# Remote.net
KiCad netlist of a schematic drawn in EAGLE
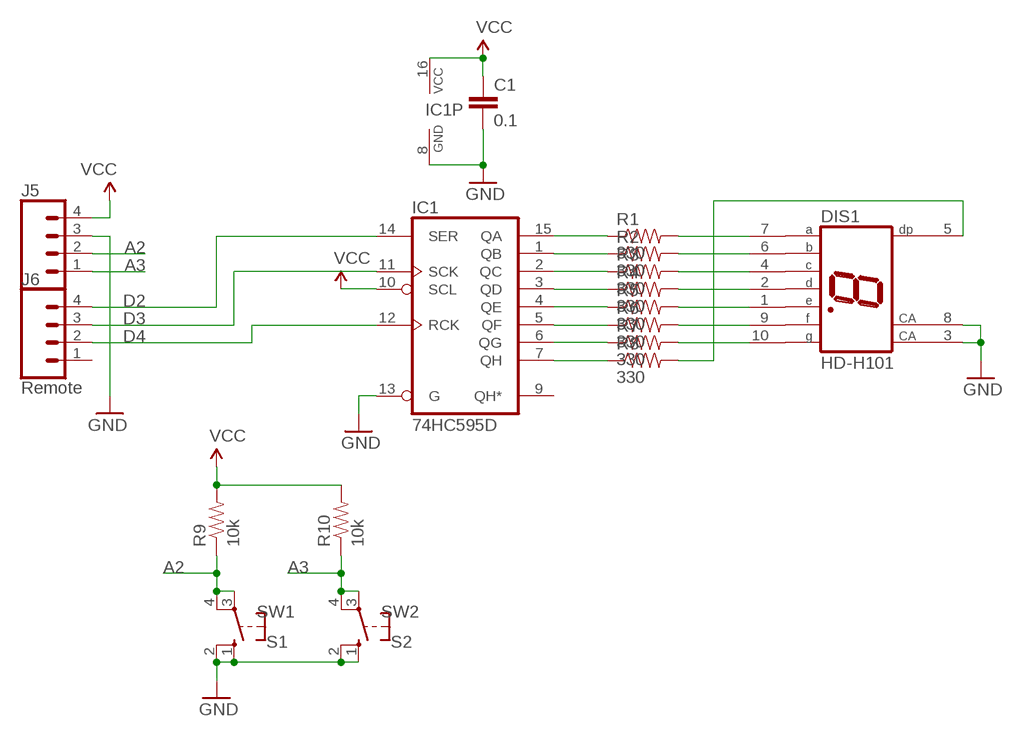
[diagram p0: schematic, sheet 1]

(export (version "E")
  (design (tool "Eeschema 10.0.6"))
  (components
    (comp (ref "C1")
      (value "0.1")
      (footprint "eagle-import:0805")
      (libsource (lib "eagle-import") (part "CAP0805"))
    )
    (comp (ref "DIS1")
      (value "HD-H101")
      (footprint "eagle-import:HDSP-M")
      (libsource (lib "eagle-import") (part "HD-H101"))
    )
    (comp (ref "IC1")
      (value "74HC595D")
      (footprint "eagle-import:SO16")
      (libsource (lib "eagle-import") (part "74595DHC"))
    )
    (comp (ref "J5")
      (value "CONN_04JST-PTH")
      (footprint "eagle-import:JST-4-PTH")
      (libsource (lib "eagle-import") (part "CONN_04JST-PTH"))
    )
    (comp (ref "J6")
      (value "Remote")
      (footprint "eagle-import:JST-4-PTH")
      (libsource (lib "eagle-import") (part "CONN_04JST-PTH"))
    )
    (comp (ref "R1")
      (value "330")
      (footprint "eagle-import:0805")
      (libsource (lib "eagle-import") (part "RESISTOR0805-RES"))
    )
    (comp (ref "R2")
      (value "330")
      (footprint "eagle-import:0805")
      (libsource (lib "eagle-import") (part "RESISTOR0805-RES"))
    )
    (comp (ref "R3")
      (value "330")
      (footprint "eagle-import:0805")
      (libsource (lib "eagle-import") (part "RESISTOR0805-RES"))
    )
    (comp (ref "R4")
      (value "330")
      (footprint "eagle-import:0805")
      (libsource (lib "eagle-import") (part "RESISTOR0805-RES"))
    )
    (comp (ref "R5")
      (value "330")
      (footprint "eagle-import:0805")
      (libsource (lib "eagle-import") (part "RESISTOR0805-RES"))
    )
    (comp (ref "R6")
      (value "330")
      (footprint "eagle-import:0805")
      (libsource (lib "eagle-import") (part "RESISTOR0805-RES"))
    )
    (comp (ref "R7")
      (value "330")
      (footprint "eagle-import:0805")
      (libsource (lib "eagle-import") (part "RESISTOR0805-RES"))
    )
    (comp (ref "R8")
      (value "330")
      (footprint "eagle-import:0805")
      (libsource (lib "eagle-import") (part "RESISTOR0805-RES"))
    )
    (comp (ref "R9")
      (value "10k")
      (footprint "eagle-import:0805")
      (libsource (lib "eagle-import") (part "RESISTOR0805-RES"))
    )
    (comp (ref "R10")
      (value "10k")
      (footprint "eagle-import:0805")
      (libsource (lib "eagle-import") (part "RESISTOR0805-RES"))
    )
    (comp (ref "S1")
      (value "SW1")
      (footprint "eagle-import:B3F-10XX")
      (fields
        (field (name "MPN") "B3F-1000")
        (field (name "MPN_1") "B3F-1000")
        (field (name "OC_FARNELL") "176432")
        (field (name "OC_NEWARK") "36M3542")
      )
      (libsource (lib "eagle-import") (part "10-XX"))
    )
    (comp (ref "S2")
      (value "SW2")
      (footprint "eagle-import:B3F-10XX")
      (fields
        (field (name "MPN") "B3F-1000")
        (field (name "MPN_1") "B3F-1000")
        (field (name "OC_FARNELL") "176432")
        (field (name "OC_NEWARK") "36M3542")
      )
      (libsource (lib "eagle-import") (part "10-XX"))
    )
  )
  (nets
    (net (code "1") (name "/A2") (class "Default")
      (node (ref "J5") (pin "2") (pinfunction "2_2") (pintype "passive"))
      (node (ref "R9") (pin "1") (pinfunction "1_1") (pintype "passive"))
      (node (ref "S1") (pin "3") (pinfunction "P_3") (pintype "passive"))
      (node (ref "S1") (pin "4") (pinfunction "P1_4") (pintype "passive"))
    )
    (net (code "2") (name "/A3") (class "Default")
      (node (ref "J5") (pin "1") (pinfunction "1_1") (pintype "passive"))
      (node (ref "R10") (pin "1") (pinfunction "1_1") (pintype "passive"))
      (node (ref "S2") (pin "3") (pinfunction "P_3") (pintype "passive"))
      (node (ref "S2") (pin "4") (pinfunction "P1_4") (pintype "passive"))
    )
    (net (code "3") (name "/D2") (class "Default")
      (node (ref "IC1") (pin "14") (pinfunction "SER_14") (pintype "input"))
      (node (ref "J6") (pin "4") (pinfunction "4_4") (pintype "passive"))
    )
    (net (code "4") (name "/D3") (class "Default")
      (node (ref "IC1") (pin "11") (pinfunction "SCK_11") (pintype "input"))
      (node (ref "J6") (pin "3") (pinfunction "3_3") (pintype "passive"))
    )
    (net (code "5") (name "/D4") (class "Default")
      (node (ref "IC1") (pin "12") (pinfunction "RCK_12") (pintype "input"))
      (node (ref "J6") (pin "2") (pinfunction "2_2") (pintype "passive"))
    )
    (net (code "6") (name "GND") (class "Default")
      (node (ref "C1") (pin "2") (pinfunction "2_2") (pintype "passive"))
      (node (ref "DIS1") (pin "3") (pinfunction "CA_3") (pintype "passive"))
      (node (ref "DIS1") (pin "8") (pinfunction "CA_8") (pintype "passive"))
      (node (ref "IC1") (pin "13") (pinfunction "G_13") (pintype "input"))
      (node (ref "IC1") (pin "8") (pinfunction "GND_8") (pintype "power_in"))
      (node (ref "J5") (pin "3") (pinfunction "3_3") (pintype "passive"))
      (node (ref "S1") (pin "1") (pinfunction "S_1") (pintype "passive"))
      (node (ref "S1") (pin "2") (pinfunction "S1_2") (pintype "passive"))
      (node (ref "S2") (pin "1") (pinfunction "S_1") (pintype "passive"))
      (node (ref "S2") (pin "2") (pinfunction "S1_2") (pintype "passive"))
    )
    (net (code "7") (name "Net-(DIS1-A)") (class "Default")
      (node (ref "DIS1") (pin "7") (pinfunction "A_7") (pintype "passive"))
      (node (ref "R1") (pin "2") (pinfunction "2_2") (pintype "passive"))
    )
    (net (code "8") (name "Net-(DIS1-B)") (class "Default")
      (node (ref "DIS1") (pin "6") (pinfunction "B_6") (pintype "passive"))
      (node (ref "R2") (pin "2") (pinfunction "2_2") (pintype "passive"))
    )
    (net (code "9") (name "Net-(DIS1-C)") (class "Default")
      (node (ref "DIS1") (pin "4") (pinfunction "C_4") (pintype "passive"))
      (node (ref "R3") (pin "2") (pinfunction "2_2") (pintype "passive"))
    )
    (net (code "10") (name "Net-(DIS1-D)") (class "Default")
      (node (ref "DIS1") (pin "2") (pinfunction "D_2") (pintype "passive"))
      (node (ref "R4") (pin "2") (pinfunction "2_2") (pintype "passive"))
    )
    (net (code "11") (name "Net-(DIS1-DP)") (class "Default")
      (node (ref "DIS1") (pin "5") (pinfunction "DP_5") (pintype "passive"))
      (node (ref "R8") (pin "2") (pinfunction "2_2") (pintype "passive"))
    )
    (net (code "12") (name "Net-(DIS1-E)") (class "Default")
      (node (ref "DIS1") (pin "1") (pinfunction "E_1") (pintype "passive"))
      (node (ref "R5") (pin "2") (pinfunction "2_2") (pintype "passive"))
    )
    (net (code "13") (name "Net-(DIS1-F)") (class "Default")
      (node (ref "DIS1") (pin "9") (pinfunction "F_9") (pintype "passive"))
      (node (ref "R6") (pin "2") (pinfunction "2_2") (pintype "passive"))
    )
    (net (code "14") (name "Net-(DIS1-G)") (class "Default")
      (node (ref "DIS1") (pin "10") (pinfunction "G_10") (pintype "passive"))
      (node (ref "R7") (pin "2") (pinfunction "2_2") (pintype "passive"))
    )
    (net (code "15") (name "Net-(IC1A-QA)") (class "Default")
      (node (ref "IC1") (pin "15") (pinfunction "QA_15") (pintype "tri_state"))
      (node (ref "R1") (pin "1") (pinfunction "1_1") (pintype "passive"))
    )
    (net (code "16") (name "Net-(IC1A-QB)") (class "Default")
      (node (ref "IC1") (pin "1") (pinfunction "QB_1") (pintype "tri_state"))
      (node (ref "R2") (pin "1") (pinfunction "1_1") (pintype "passive"))
    )
    (net (code "17") (name "Net-(IC1A-QC)") (class "Default")
      (node (ref "IC1") (pin "2") (pinfunction "QC_2") (pintype "tri_state"))
      (node (ref "R3") (pin "1") (pinfunction "1_1") (pintype "passive"))
    )
    (net (code "18") (name "Net-(IC1A-QD)") (class "Default")
      (node (ref "IC1") (pin "3") (pinfunction "QD_3") (pintype "tri_state"))
      (node (ref "R4") (pin "1") (pinfunction "1_1") (pintype "passive"))
    )
    (net (code "19") (name "Net-(IC1A-QE)") (class "Default")
      (node (ref "IC1") (pin "4") (pinfunction "QE_4") (pintype "tri_state"))
      (node (ref "R5") (pin "1") (pinfunction "1_1") (pintype "passive"))
    )
    (net (code "20") (name "Net-(IC1A-QF)") (class "Default")
      (node (ref "IC1") (pin "5") (pinfunction "QF_5") (pintype "tri_state"))
      (node (ref "R6") (pin "1") (pinfunction "1_1") (pintype "passive"))
    )
    (net (code "21") (name "Net-(IC1A-QG)") (class "Default")
      (node (ref "IC1") (pin "6") (pinfunction "QG_6") (pintype "tri_state"))
      (node (ref "R7") (pin "1") (pinfunction "1_1") (pintype "passive"))
    )
    (net (code "22") (name "Net-(IC1A-QH)") (class "Default")
      (node (ref "IC1") (pin "7") (pinfunction "QH_7") (pintype "tri_state"))
      (node (ref "R8") (pin "1") (pinfunction "1_1") (pintype "passive"))
    )
    (net (code "23") (name "VCC") (class "Default")
      (node (ref "C1") (pin "1") (pinfunction "1_1") (pintype "passive"))
      (node (ref "IC1") (pin "10") (pinfunction "SCL_10") (pintype "input"))
      (node (ref "IC1") (pin "16") (pinfunction "VCC_16") (pintype "power_in"))
      (node (ref "J5") (pin "4") (pinfunction "4_4") (pintype "passive"))
      (node (ref "R10") (pin "2") (pinfunction "2_2") (pintype "passive"))
      (node (ref "R9") (pin "2") (pinfunction "2_2") (pintype "passive"))
    )
    (net (code "24") (name "unconnected-(IC1A-QH*-Pad9)") (class "Default")
      (node (ref "IC1") (pin "9") (pinfunction "QH*_9") (pintype "tri_state"))
    )
    (net (code "25") (name "unconnected-(J6-Pad1)") (class "Default")
      (node (ref "J6") (pin "1") (pinfunction "1_1") (pintype "passive"))
    )
  )
)
